# CH32V307V-R1-1v0.net
KiCad netlist of a schematic drawn in Altium Designer
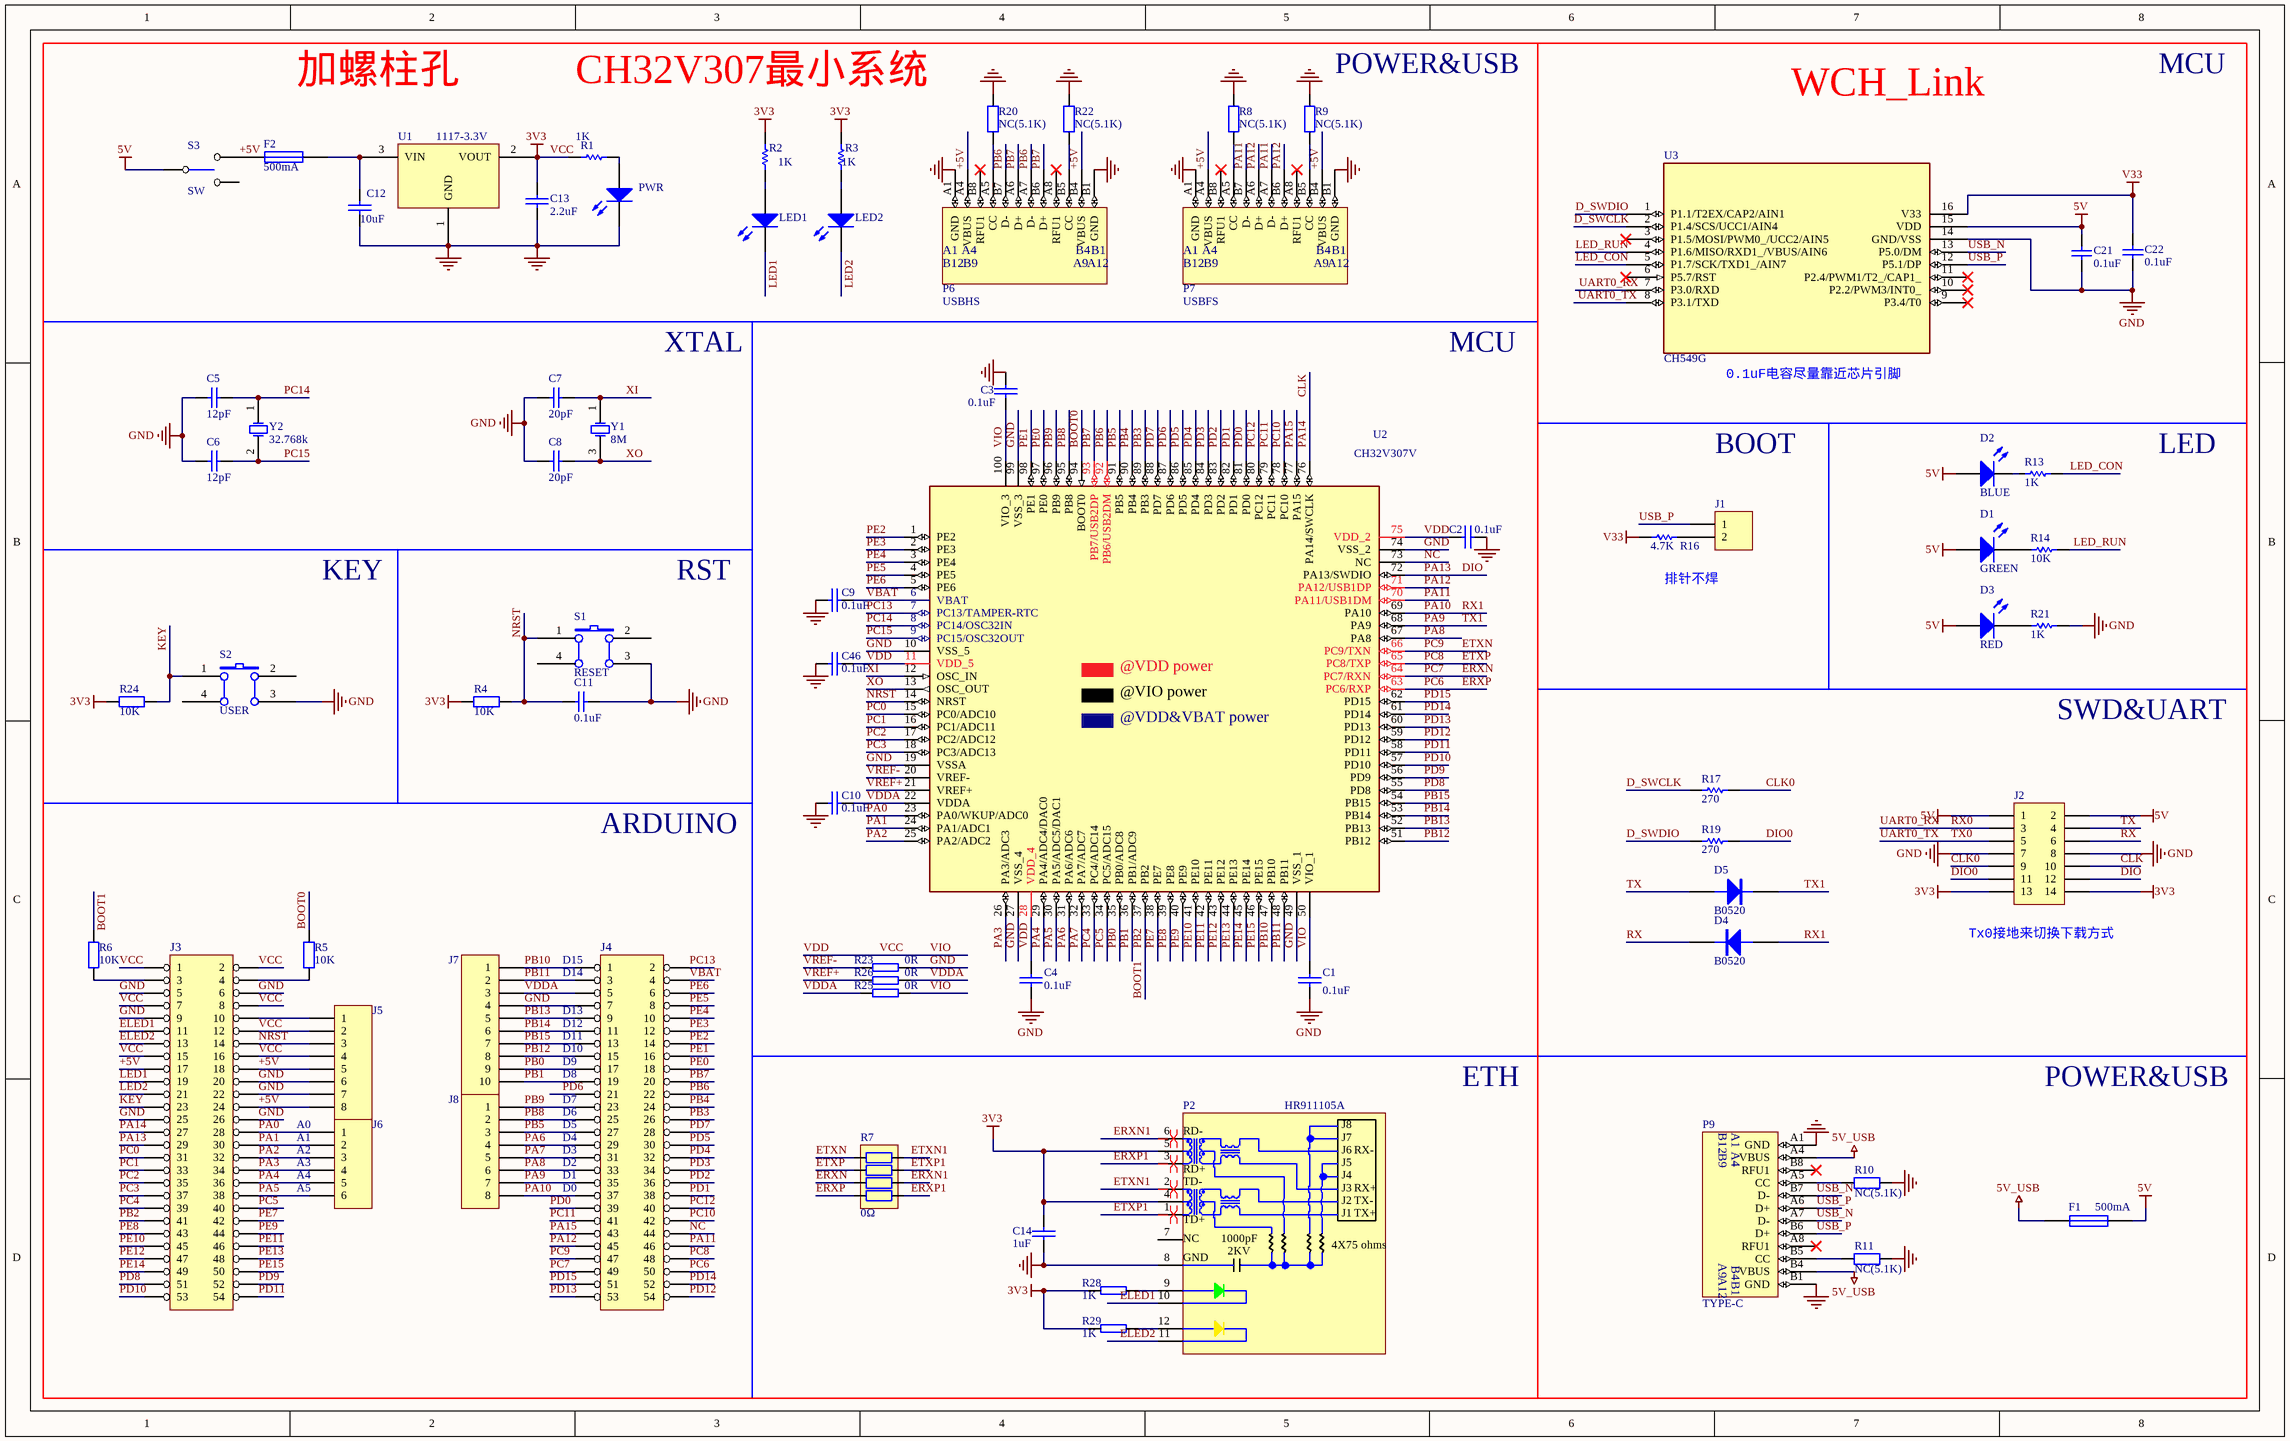
[diagram p0: CH32V307V-R1-1v0.SchDoc]

(export (version "E")
  (design (tool "Eeschema 10.0.6"))
  (components
    (comp (ref "C1")
      (value "0.1uF")
      (footprint "0603_C")
      (description "Capacitor")
      (libsource (lib "*") (part "CAP"))
    )
    (comp (ref "C2")
      (value "0.1uF")
      (footprint "0603_C")
      (description "Capacitor")
      (libsource (lib "*") (part "CAP"))
    )
    (comp (ref "C3")
      (value "0.1uF")
      (footprint "0603_C")
      (description "Capacitor")
      (libsource (lib "*") (part "CAP"))
    )
    (comp (ref "C4")
      (value "0.1uF")
      (footprint "0603_C")
      (description "Capacitor")
      (libsource (lib "*") (part "CAP"))
    )
    (comp (ref "C5")
      (value "12pF")
      (footprint "0603_C")
      (description "Capacitor")
      (libsource (lib "Miscellaneous Devices") (part "Cap"))
    )
    (comp (ref "C6")
      (value "12pF")
      (footprint "0603_C")
      (description "Capacitor")
      (libsource (lib "Miscellaneous Devices") (part "Cap"))
    )
    (comp (ref "C7")
      (value "20pF")
      (footprint "0603_C")
      (description "Capacitor")
      (libsource (lib "Miscellaneous Devices") (part "Cap"))
    )
    (comp (ref "C8")
      (value "20pF")
      (footprint "0603_C")
      (description "Capacitor")
      (libsource (lib "Miscellaneous Devices") (part "Cap"))
    )
    (comp (ref "C9")
      (value "0.1uF")
      (footprint "0603_C")
      (description "Capacitor")
      (libsource (lib "*") (part "CAP"))
    )
    (comp (ref "C10")
      (value "0.1uF")
      (footprint "0603_C")
      (description "Capacitor")
      (libsource (lib "*") (part "CAP"))
    )
    (comp (ref "C11")
      (value "0.1uF")
      (footprint "0603_C")
      (description "Capacitor")
      (libsource (lib "Miscellaneous Devices") (part "Cap"))
    )
    (comp (ref "C12")
      (value "10uF")
      (footprint "3216_C")
      (description "Capacitor")
      (libsource (lib "*") (part "CAP"))
    )
    (comp (ref "C13")
      (value "2.2uF")
      (footprint "0603_C")
      (description "Capacitor")
      (libsource (lib "*") (part "CAP"))
    )
    (comp (ref "C14")
      (value "1uF")
      (footprint "0603_C")
      (description "Capacitor")
      (libsource (lib "*") (part "CAP"))
    )
    (comp (ref "C21")
      (value "0.1uF")
      (footprint "0603_C")
      (description "Capacitor")
      (fields (field (name "PUBLISHER") "Altium Limited"))
      (libsource (lib "MYLIB") (part "C-RAD-0603"))
    )
    (comp (ref "C22")
      (value "0.1uF")
      (footprint "0603_C")
      (description "Capacitor")
      (fields (field (name "PUBLISHER") "Altium Limited"))
      (libsource (lib "MYLIB") (part "C-RAD-0603"))
    )
    (comp (ref "C46")
      (value "0.1uF")
      (footprint "0603_C")
      (description "Capacitor")
      (libsource (lib "*") (part "CAP"))
    )
    (comp (ref "D1")
      (value "GREEN")
      (footprint "0603+")
      (description "Typical RED, GREEN, YELLOW, AMBER GaAs LED")
      (fields (field (name "PUBLISHER") "Altium Limited"))
      (libsource (lib "MYLIB") (part "D0603"))
    )
    (comp (ref "D2")
      (value "BLUE")
      (footprint "0603+")
      (description "Typical RED, GREEN, YELLOW, AMBER GaAs LED")
      (fields (field (name "PUBLISHER") "Altium Limited"))
      (libsource (lib "MYLIB") (part "D0603"))
    )
    (comp (ref "D3")
      (value "RED")
      (footprint "0603+")
      (description "Typical RED, GREEN, YELLOW, AMBER GaAs LED")
      (fields (field (name "PUBLISHER") "Altium Limited"))
      (libsource (lib "MYLIB") (part "D0603"))
    )
    (comp (ref "D4")
      (value "B0520")
      (footprint "SOD-323")
      (description "Diode")
      (libsource (lib "*") (part "DIODE"))
    )
    (comp (ref "D5")
      (value "B0520")
      (footprint "SOD-323")
      (description "Diode")
      (libsource (lib "*") (part "DIODE"))
    )
    (comp (ref "F1")
      (value "500mA")
      (footprint "0805")
      (description "Fuse")
      (libsource (lib "*") (part "FUSE1"))
    )
    (comp (ref "F2")
      (value "500mA")
      (footprint "0805")
      (description "Fuse")
      (libsource (lib "*") (part "FUSE1"))
    )
    (comp (ref "J1")
      (value "Header 2")
      (footprint "SIP2-2.54MM")
      (description "Header, 2-Pin")
      (fields (field (name "PUBLISHER") "Altium Limited"))
      (libsource (lib "Miscellaneous Connectors") (part "Header 2"))
    )
    (comp (ref "J2")
      (value "Header 7X2")
      (footprint "IDC14-2.54mm")
      (description "Header, 7-Pin, Dual row")
      (fields (field (name "PUBLISHER") "Altium Limited"))
      (libsource (lib "Miscellaneous Connectors") (part "Header 7X2"))
    )
    (comp (ref "J3")
      (value "HEADER 27x2")
      (footprint "MYPCB:IDC54-2.54MM")
      (description "Header, 27-Pin, Dual row")
      (libsource (lib "wch_sch_others") (part "HEADER 27x2"))
    )
    (comp (ref "J4")
      (value "HEADER 27x2")
      (footprint "MYPCB:IDC54-2.54MM")
      (description "Header, 27-Pin, Dual row")
      (libsource (lib "wch_sch_others") (part "HEADER 27x2"))
    )
    (comp (ref "J5")
      (value "Header 8")
      (footprint "SIP8-2.54mm")
      (description "Header, 8-Pin")
      (fields (field (name "PUBLISHER") "Altium Limited"))
      (libsource (lib "") (part "Header 8_1"))
    )
    (comp (ref "J6")
      (value "Header 6")
      (footprint "SIP6-2.54MM")
      (description "Header, 6-Pin")
      (fields (field (name "PUBLISHER") "Altium Limited"))
      (libsource (lib "Miscellaneous Connectors") (part "Header 6"))
    )
    (comp (ref "J7")
      (value "Header 10")
      (footprint "SIP10-2.54mm")
      (description "Header, 10-Pin")
      (fields (field (name "PUBLISHER") "Altium Limited"))
      (libsource (lib "Miscellaneous Connectors") (part "Header 10"))
    )
    (comp (ref "J8")
      (value "Header 8")
      (footprint "SIP8-2.54mm")
      (description "Header, 8-Pin")
      (fields (field (name "PUBLISHER") "Altium Limited"))
      (libsource (lib "Miscellaneous Connectors") (part "Header 8"))
    )
    (comp (ref "LED1")
      (value "LED1   blue")
      (footprint "0603+")
      (description "Typical INFRARED GaAs LED")
      (fields (field (name "PUBLISHER") "Altium Limited"))
      (libsource (lib "Miscellaneous Devices") (part "LED0"))
    )
    (comp (ref "LED2")
      (value "LED2  blue")
      (footprint "0603+")
      (description "Typical INFRARED GaAs LED")
      (fields (field (name "PUBLISHER") "Altium Limited"))
      (libsource (lib "Miscellaneous Devices") (part "LED0"))
    )
    (comp (ref "P2") (value "HR911105A") (footprint "HR911105A") (libsource (lib "*") (part "HR911105A")))
    (comp (ref "P6")
      (value "USBHS")
      (footprint "TYPE-C-Receptacle-2.0")
      (libsource (lib "") (part "TYPE-C1_1"))
    )
    (comp (ref "P7")
      (value "USBFS")
      (footprint "TYPE-C-Receptacle-2.0")
      (libsource (lib "") (part "TYPE-C1_1"))
    )
    (comp (ref "P9")
      (value "TYPE-C")
      (footprint "TYPE-C-Receptacle-2.0")
      (libsource (lib "*") (part "TYPE-C1"))
    )
    (comp (ref "PWR")
      (value "POWER  red")
      (footprint "0603+")
      (description "Typical INFRARED GaAs LED")
      (fields (field (name "PUBLISHER") "Altium Limited"))
      (libsource (lib "Miscellaneous Devices") (part "LED0"))
    )
    (comp (ref "R1")
      (value "1K")
      (footprint "0603")
      (description "Semiconductor Resistor")
      (libsource (lib "Miscellaneous Devices") (part "Res Semi"))
    )
    (comp (ref "R2")
      (value "1K")
      (footprint "0603")
      (description "Semiconductor Resistor")
      (libsource (lib "Miscellaneous Devices") (part "Res Semi"))
    )
    (comp (ref "R3")
      (value "1K")
      (footprint "0603")
      (description "Semiconductor Resistor")
      (libsource (lib "Miscellaneous Devices") (part "Res Semi"))
    )
    (comp (ref "R4")
      (value "10K")
      (footprint "0603")
      (description "Resistor")
      (libsource (lib "") (part "Res2_2"))
    )
    (comp (ref "R5")
      (value "10K")
      (footprint "0603")
      (description "Resistor")
      (libsource (lib "") (part "Res2_1"))
    )
    (comp (ref "R6")
      (value "10K")
      (footprint "0603")
      (description "Resistor")
      (libsource (lib "Miscellaneous Devices") (part "Res2"))
    )
    (comp (ref "R7")
      (value "0Ω")
      (footprint "RCA-8P4R-0603")
      (description "贴片网络排阻")
      (fields (field (name "版权归属") "源创客"))
      (libsource (lib "wch_sch_others") (part "R-8P4R"))
    )
    (comp (ref "R8")
      (value "NC(5.1K)")
      (footprint "0603")
      (description "Resistor")
      (libsource (lib "Miscellaneous Devices") (part "Res2"))
    )
    (comp (ref "R9")
      (value "NC(5.1K)")
      (footprint "0603")
      (description "Resistor")
      (libsource (lib "Miscellaneous Devices") (part "Res2"))
    )
    (comp (ref "R10")
      (value "NC(5.1K)")
      (footprint "0603")
      (description "Resistor")
      (libsource (lib "") (part "Res2_3"))
    )
    (comp (ref "R11")
      (value "NC(5.1K)")
      (footprint "0603")
      (description "Resistor")
      (libsource (lib "") (part "Res2_3"))
    )
    (comp (ref "R13")
      (value "1K")
      (footprint "0603")
      (description "Resistor")
      (fields (field (name "PUBLISHER") "Altium Limited"))
      (libsource (lib "MYLIB") (part "0603-1"))
    )
    (comp (ref "R14")
      (value "10K")
      (footprint "0603")
      (description "Resistor")
      (fields (field (name "PUBLISHER") "Altium Limited"))
      (libsource (lib "MYLIB") (part "0603-1"))
    )
    (comp (ref "R16")
      (value "4.7K")
      (footprint "0603")
      (description "Resistor")
      (fields (field (name "PUBLISHER") "Altium Limited"))
      (libsource (lib "MYLIB") (part "0603-1"))
    )
    (comp (ref "R17")
      (value "270")
      (footprint "0603")
      (description "Resistor")
      (fields (field (name "PUBLISHER") "Altium Limited"))
      (libsource (lib "MYLIB") (part "0603-1"))
    )
    (comp (ref "R19")
      (value "270")
      (footprint "0603")
      (description "Resistor")
      (fields (field (name "PUBLISHER") "Altium Limited"))
      (libsource (lib "MYLIB") (part "0603-1"))
    )
    (comp (ref "R20")
      (value "NC(5.1K)")
      (footprint "0603")
      (description "Resistor")
      (libsource (lib "Miscellaneous Devices") (part "Res2"))
    )
    (comp (ref "R21")
      (value "1K")
      (footprint "0603")
      (description "Resistor")
      (fields (field (name "PUBLISHER") "Altium Limited"))
      (libsource (lib "MYLIB") (part "0603-1"))
    )
    (comp (ref "R22")
      (value "NC(5.1K)")
      (footprint "0603")
      (description "Resistor")
      (libsource (lib "Miscellaneous Devices") (part "Res2"))
    )
    (comp (ref "R23") (value "0R") (footprint "0603") (libsource (lib "*") (part "R")))
    (comp (ref "R24")
      (value "10K")
      (footprint "0603")
      (description "Resistor")
      (libsource (lib "") (part "Res2_2"))
    )
    (comp (ref "R25") (value "0R") (footprint "0603") (libsource (lib "*") (part "R")))
    (comp (ref "R26") (value "0R") (footprint "0603") (libsource (lib "*") (part "R")))
    (comp (ref "R28") (value "1K") (footprint "0603") (libsource (lib "wch_sch_others") (part "RES")))
    (comp (ref "R29") (value "1K") (footprint "0603") (libsource (lib "wch_sch_others") (part "RES")))
    (comp (ref "S1")
      (value "RESET")
      (footprint "KEYX")
      (description "SE PUSHBUTTON")
      (libsource (lib "Documents") (part "SW PUSHBUTTON"))
    )
    (comp (ref "S2")
      (value "USER")
      (footprint "KEYX")
      (description "SE PUSHBUTTON")
      (libsource (lib "Documents") (part "SW PUSHBUTTON"))
    )
    (comp (ref "S3") (value "SW") (footprint "KEY2") (libsource (lib "MYSCH") (part "SW")))
    (comp (ref "U1")
      (value "1117-3.3V")
      (footprint "SOT-223")
      (libsource (lib "wch_sch_others") (part "1117-3.3V"))
    )
    (comp (ref "U2")
      (value "CH32V307V")
      (footprint "LQFP100")
      (description "RISC-V FPU MCU, 144MHz, USB_480M，USB OTG,1000M Ethernet MAC, 2*CAN")
      (libsource (lib "CHXXX") (part "CH32V307V"))
    )
    (comp (ref "U3")
      (value "CH549G")
      (footprint "SOP16")
      (description "8bit MCS51 MCU with ADC & USB type-C host & device & dual UART & SPI")
      (libsource (lib "CHXXXSCH(1)") (part "CH549G"))
    )
    (comp (ref "Y1")
      (value "8M")
      (footprint "XT3225")
      (description "Crystal Oscillator")
      (fields (field (name "PUBLISHER") "Altium Limited"))
      (libsource (lib "") (part "XTAL_1"))
    )
    (comp (ref "Y2")
      (value "32.768k")
      (footprint "FC-135")
      (description "Crystal Oscillator")
      (fields (field (name "PUBLISHER") "Altium Limited"))
      (libsource (lib "Miscellaneous Devices") (part "XTAL"))
    )
  )
  (nets
    (net (code "1") (name "/+5V") (class "Default")
      (node (ref "F2") (pin "1") (pinfunction "1_1") (pintype "passive"))
      (node (ref "J3") (pin "17") (pinfunction "17_17") (pintype "passive"))
      (node (ref "J3") (pin "18") (pinfunction "18_18") (pintype "passive"))
      (node (ref "J3") (pin "24") (pinfunction "24_24") (pintype "passive"))
      (node (ref "J5") (pin "5") (pinfunction "5_5") (pintype "passive"))
      (node (ref "J5") (pin "8") (pinfunction "8_8") (pintype "passive"))
      (node (ref "P6") (pin "A4") (pinfunction "VBUS_A4") (pintype "bidirectional"))
      (node (ref "P6") (pin "B4") (pinfunction "VBUS_B4") (pintype "bidirectional"))
      (node (ref "P7") (pin "A4") (pinfunction "VBUS_A4") (pintype "bidirectional"))
      (node (ref "P7") (pin "B4") (pinfunction "VBUS_B4") (pintype "bidirectional"))
      (node (ref "S3") (pin "3") (pinfunction "3_3") (pintype "passive"))
    )
    (net (code "2") (name "/BOOT0") (class "Default")
      (node (ref "R5") (pin "2") (pinfunction "2_2") (pintype "passive"))
      (node (ref "U2") (pin "94") (pinfunction "BOOT0_94") (pintype "input"))
    )
    (net (code "3") (name "/BOOT1") (class "Default")
      (node (ref "J3") (pin "41") (pinfunction "41_41") (pintype "passive"))
      (node (ref "R6") (pin "1") (pinfunction "1_1") (pintype "passive"))
      (node (ref "U2") (pin "37") (pinfunction "PB2_37") (pintype "bidirectional"))
    )
    (net (code "4") (name "/CLK") (class "Default")
      (node (ref "J2") (pin "10") (pinfunction "10_10") (pintype "passive"))
      (node (ref "J3") (pin "27") (pinfunction "27_27") (pintype "passive"))
      (node (ref "U2") (pin "76") (pinfunction "PA14/SWCLK_76") (pintype "bidirectional"))
    )
    (net (code "5") (name "/CLK0") (class "Default")
      (node (ref "J2") (pin "9") (pinfunction "9_9") (pintype "passive"))
      (node (ref "R17") (pin "1") (pinfunction "1_1") (pintype "passive"))
    )
    (net (code "6") (name "/DIO") (class "Default")
      (node (ref "J2") (pin "12") (pinfunction "12_12") (pintype "passive"))
      (node (ref "J3") (pin "29") (pinfunction "29_29") (pintype "passive"))
      (node (ref "U2") (pin "72") (pinfunction "PA13/SWDIO_72") (pintype "bidirectional"))
    )
    (net (code "7") (name "/DIO0") (class "Default")
      (node (ref "J2") (pin "11") (pinfunction "11_11") (pintype "passive"))
      (node (ref "R19") (pin "1") (pinfunction "1_1") (pintype "passive"))
    )
    (net (code "8") (name "/D_SWCLK") (class "Default")
      (node (ref "R17") (pin "2") (pinfunction "2_2") (pintype "passive"))
      (node (ref "U3") (pin "2") (pinfunction "P1.4/SCS/UCC1/AIN4_2") (pintype "bidirectional"))
    )
    (net (code "9") (name "/D_SWDIO") (class "Default")
      (node (ref "R19") (pin "2") (pinfunction "2_2") (pintype "passive"))
      (node (ref "U3") (pin "1") (pinfunction "P1.1/T2EX/CAP2/AIN1_1") (pintype "bidirectional"))
    )
    (net (code "10") (name "/ELED1") (class "Default")
      (node (ref "J3") (pin "11") (pinfunction "11_11") (pintype "passive"))
      (node (ref "P2") (pin "10") (pintype "passive"))
    )
    (net (code "11") (name "/ELED2") (class "Default")
      (node (ref "J3") (pin "13") (pinfunction "13_13") (pintype "passive"))
      (node (ref "P2") (pin "11") (pintype "passive"))
    )
    (net (code "12") (name "/ERXN") (class "Default")
      (node (ref "J4") (pin "49") (pinfunction "49_49") (pintype "passive"))
      (node (ref "R7") (pin "3") (pinfunction "3_3") (pintype "passive"))
      (node (ref "U2") (pin "64") (pinfunction "PC7/RXN_64") (pintype "bidirectional"))
    )
    (net (code "13") (name "/ERXN1") (class "Default")
      (node (ref "P2") (pin "6") (pintype "passive"))
      (node (ref "R7") (pin "6") (pinfunction "6_6") (pintype "passive"))
    )
    (net (code "14") (name "/ERXP") (class "Default")
      (node (ref "J4") (pin "50") (pinfunction "50_50") (pintype "passive"))
      (node (ref "R7") (pin "4") (pinfunction "4_4") (pintype "passive"))
      (node (ref "U2") (pin "63") (pinfunction "PC6/RXP_63") (pintype "bidirectional"))
    )
    (net (code "15") (name "/ERXP1") (class "Default")
      (node (ref "P2") (pin "3") (pintype "passive"))
      (node (ref "R7") (pin "5") (pinfunction "5_5") (pintype "passive"))
    )
    (net (code "16") (name "/ETXN") (class "Default")
      (node (ref "J4") (pin "47") (pinfunction "47_47") (pintype "passive"))
      (node (ref "R7") (pin "1") (pinfunction "1_1") (pintype "passive"))
      (node (ref "U2") (pin "66") (pinfunction "PC9/TXN_66") (pintype "bidirectional"))
    )
    (net (code "17") (name "/ETXN1") (class "Default")
      (node (ref "P2") (pin "2") (pintype "passive"))
      (node (ref "R7") (pin "8") (pinfunction "8_8") (pintype "passive"))
    )
    (net (code "18") (name "/ETXP") (class "Default")
      (node (ref "J4") (pin "48") (pinfunction "48_48") (pintype "passive"))
      (node (ref "R7") (pin "2") (pinfunction "2_2") (pintype "passive"))
      (node (ref "U2") (pin "65") (pinfunction "PC8/TXP_65") (pintype "bidirectional"))
    )
    (net (code "19") (name "/ETXP1") (class "Default")
      (node (ref "P2") (pin "1") (pintype "passive"))
      (node (ref "R7") (pin "7") (pinfunction "7_7") (pintype "passive"))
    )
    (net (code "20") (name "/KEY") (class "Default")
      (node (ref "J3") (pin "23") (pinfunction "23_23") (pintype "passive"))
      (node (ref "R24") (pin "1") (pinfunction "1_1") (pintype "passive"))
      (node (ref "S2") (pin "1") (pinfunction "A0_1") (pintype "passive"))
    )
    (net (code "21") (name "/LED1") (class "Default")
      (node (ref "J3") (pin "19") (pinfunction "19_19") (pintype "passive"))
      (node (ref "LED1") (pin "2") (pinfunction "K_2") (pintype "passive"))
    )
    (net (code "22") (name "/LED2") (class "Default")
      (node (ref "J3") (pin "21") (pinfunction "21_21") (pintype "passive"))
      (node (ref "LED2") (pin "2") (pinfunction "K_2") (pintype "passive"))
    )
    (net (code "23") (name "/LED_CON") (class "Default")
      (node (ref "R13") (pin "1") (pinfunction "1_1") (pintype "passive"))
      (node (ref "U3") (pin "5") (pinfunction "P1.7/SCK/TXD1_/AIN7_5") (pintype "bidirectional"))
    )
    (net (code "24") (name "/LED_RUN") (class "Default")
      (node (ref "R14") (pin "1") (pinfunction "1_1") (pintype "passive"))
      (node (ref "U3") (pin "4") (pinfunction "P1.6/MISO/RXD1_/VBUS/AIN6_4") (pintype "bidirectional"))
    )
    (net (code "25") (name "/NC") (class "Default")
      (node (ref "J4") (pin "44") (pinfunction "44_44") (pintype "passive"))
      (node (ref "U2") (pin "73") (pinfunction "NC_73") (pintype "tri_state"))
    )
    (net (code "26") (name "/NRST") (class "Default")
      (node (ref "C11") (pin "2") (pinfunction "2_2") (pintype "passive"))
      (node (ref "J3") (pin "14") (pinfunction "14_14") (pintype "passive"))
      (node (ref "J5") (pin "3") (pinfunction "3_3") (pintype "passive"))
      (node (ref "R4") (pin "1") (pinfunction "1_1") (pintype "passive"))
      (node (ref "S1") (pin "1") (pinfunction "A0_1") (pintype "passive"))
      (node (ref "U2") (pin "14") (pinfunction "NRST_14") (pintype "bidirectional"))
    )
    (net (code "27") (name "/PA0") (class "Default")
      (node (ref "J3") (pin "28") (pinfunction "28_28") (pintype "passive"))
      (node (ref "J6") (pin "1") (pinfunction "1_1") (pintype "passive"))
      (node (ref "U2") (pin "23") (pinfunction "PA0/WKUP/ADC0_23") (pintype "bidirectional"))
    )
    (net (code "28") (name "/PA1") (class "Default")
      (node (ref "J3") (pin "30") (pinfunction "30_30") (pintype "passive"))
      (node (ref "J6") (pin "2") (pinfunction "2_2") (pintype "passive"))
      (node (ref "U2") (pin "24") (pinfunction "PA1/ADC1_24") (pintype "bidirectional"))
    )
    (net (code "29") (name "/PA2") (class "Default")
      (node (ref "J3") (pin "32") (pinfunction "32_32") (pintype "passive"))
      (node (ref "J6") (pin "3") (pinfunction "3_3") (pintype "passive"))
      (node (ref "U2") (pin "25") (pinfunction "PA2/ADC2_25") (pintype "bidirectional"))
    )
    (net (code "30") (name "/PA3") (class "Default")
      (node (ref "J3") (pin "34") (pinfunction "34_34") (pintype "passive"))
      (node (ref "J6") (pin "4") (pinfunction "4_4") (pintype "passive"))
      (node (ref "U2") (pin "26") (pinfunction "PA3/ADC3_26") (pintype "bidirectional"))
    )
    (net (code "31") (name "/PA4") (class "Default")
      (node (ref "J3") (pin "36") (pinfunction "36_36") (pintype "passive"))
      (node (ref "J6") (pin "5") (pinfunction "5_5") (pintype "passive"))
      (node (ref "U2") (pin "29") (pinfunction "PA4/ADC4/DAC0_29") (pintype "bidirectional"))
    )
    (net (code "32") (name "/PA5") (class "Default")
      (node (ref "J3") (pin "38") (pinfunction "38_38") (pintype "passive"))
      (node (ref "J6") (pin "6") (pinfunction "6_6") (pintype "passive"))
      (node (ref "U2") (pin "30") (pinfunction "PA5/ADC5/DAC1_30") (pintype "bidirectional"))
    )
    (net (code "33") (name "/PA6") (class "Default")
      (node (ref "J4") (pin "29") (pinfunction "29_29") (pintype "passive"))
      (node (ref "J8") (pin "4") (pinfunction "4_4") (pintype "passive"))
      (node (ref "U2") (pin "31") (pinfunction "PA6/ADC6_31") (pintype "bidirectional"))
    )
    (net (code "34") (name "/PA7") (class "Default")
      (node (ref "J4") (pin "31") (pinfunction "31_31") (pintype "passive"))
      (node (ref "J8") (pin "5") (pinfunction "5_5") (pintype "passive"))
      (node (ref "U2") (pin "32") (pinfunction "PA7/ADC7_32") (pintype "bidirectional"))
    )
    (net (code "35") (name "/PA8") (class "Default")
      (node (ref "J4") (pin "33") (pinfunction "33_33") (pintype "passive"))
      (node (ref "J8") (pin "6") (pinfunction "6_6") (pintype "passive"))
      (node (ref "U2") (pin "67") (pinfunction "PA8_67") (pintype "bidirectional"))
    )
    (net (code "36") (name "/PA9") (class "Default")
      (node (ref "D5") (pin "2") (pinfunction "K_2") (pintype "passive"))
      (node (ref "J4") (pin "35") (pinfunction "35_35") (pintype "passive"))
      (node (ref "J8") (pin "7") (pinfunction "7_7") (pintype "passive"))
      (node (ref "U2") (pin "68") (pinfunction "PA9_68") (pintype "bidirectional"))
    )
    (net (code "37") (name "/PA10") (class "Default")
      (node (ref "D4") (pin "1") (pinfunction "A_1") (pintype "passive"))
      (node (ref "J4") (pin "37") (pinfunction "37_37") (pintype "passive"))
      (node (ref "J8") (pin "8") (pinfunction "8_8") (pintype "passive"))
      (node (ref "U2") (pin "69") (pinfunction "PA10_69") (pintype "bidirectional"))
    )
    (net (code "38") (name "/PA11") (class "Default")
      (node (ref "J4") (pin "46") (pinfunction "46_46") (pintype "passive"))
      (node (ref "P7") (pin "A7") (pinfunction "D-_A7") (pintype "bidirectional"))
      (node (ref "P7") (pin "B7") (pinfunction "D-_B7") (pintype "bidirectional"))
      (node (ref "U2") (pin "70") (pinfunction "PA11/USB1DM_70") (pintype "bidirectional"))
    )
    (net (code "39") (name "/PA12") (class "Default")
      (node (ref "J4") (pin "45") (pinfunction "45_45") (pintype "passive"))
      (node (ref "P7") (pin "A6") (pinfunction "D+_A6") (pintype "bidirectional"))
      (node (ref "P7") (pin "B6") (pinfunction "D+_B6") (pintype "bidirectional"))
      (node (ref "U2") (pin "71") (pinfunction "PA12/USB1DP_71") (pintype "bidirectional"))
    )
    (net (code "40") (name "/PA15") (class "Default")
      (node (ref "J4") (pin "43") (pinfunction "43_43") (pintype "passive"))
      (node (ref "U2") (pin "77") (pinfunction "PA15_77") (pintype "bidirectional"))
    )
    (net (code "41") (name "/PB0") (class "Default")
      (node (ref "J4") (pin "17") (pinfunction "17_17") (pintype "passive"))
      (node (ref "J7") (pin "9") (pinfunction "9_9") (pintype "passive"))
      (node (ref "U2") (pin "35") (pinfunction "PB0/ADC8_35") (pintype "bidirectional"))
    )
    (net (code "42") (name "/PB1") (class "Default")
      (node (ref "J4") (pin "19") (pinfunction "19_19") (pintype "passive"))
      (node (ref "J7") (pin "10") (pinfunction "10_10") (pintype "passive"))
      (node (ref "U2") (pin "36") (pinfunction "PB1/ADC9_36") (pintype "bidirectional"))
    )
    (net (code "43") (name "/PB3") (class "Default")
      (node (ref "J4") (pin "26") (pinfunction "26_26") (pintype "passive"))
      (node (ref "U2") (pin "89") (pinfunction "PB3_89") (pintype "bidirectional"))
    )
    (net (code "44") (name "/PB4") (class "Default")
      (node (ref "J4") (pin "24") (pinfunction "24_24") (pintype "passive"))
      (node (ref "U2") (pin "90") (pinfunction "PB4_90") (pintype "bidirectional"))
    )
    (net (code "45") (name "/PB5") (class "Default")
      (node (ref "J4") (pin "27") (pinfunction "27_27") (pintype "passive"))
      (node (ref "J8") (pin "3") (pinfunction "3_3") (pintype "passive"))
      (node (ref "U2") (pin "91") (pinfunction "PB5_91") (pintype "bidirectional"))
    )
    (net (code "46") (name "/PB6") (class "Default")
      (node (ref "J4") (pin "22") (pinfunction "22_22") (pintype "passive"))
      (node (ref "P6") (pin "A7") (pinfunction "D-_A7") (pintype "bidirectional"))
      (node (ref "P6") (pin "B7") (pinfunction "D-_B7") (pintype "bidirectional"))
      (node (ref "U2") (pin "92") (pinfunction "PB6/USB2DM_92") (pintype "bidirectional"))
    )
    (net (code "47") (name "/PB7") (class "Default")
      (node (ref "J4") (pin "20") (pinfunction "20_20") (pintype "passive"))
      (node (ref "P6") (pin "A6") (pinfunction "D+_A6") (pintype "bidirectional"))
      (node (ref "P6") (pin "B6") (pinfunction "D+_B6") (pintype "bidirectional"))
      (node (ref "U2") (pin "93") (pinfunction "PB7/USB2DP_93") (pintype "bidirectional"))
    )
    (net (code "48") (name "/PB8") (class "Default")
      (node (ref "J4") (pin "25") (pinfunction "25_25") (pintype "passive"))
      (node (ref "J8") (pin "2") (pinfunction "2_2") (pintype "passive"))
      (node (ref "U2") (pin "95") (pinfunction "PB8_95") (pintype "bidirectional"))
    )
    (net (code "49") (name "/PB9") (class "Default")
      (node (ref "J4") (pin "23") (pinfunction "23_23") (pintype "passive"))
      (node (ref "J8") (pin "1") (pinfunction "1_1") (pintype "passive"))
      (node (ref "U2") (pin "96") (pinfunction "PB9_96") (pintype "bidirectional"))
    )
    (net (code "50") (name "/PB10") (class "Default")
      (node (ref "J4") (pin "1") (pinfunction "1_1") (pintype "passive"))
      (node (ref "J7") (pin "1") (pinfunction "1_1") (pintype "passive"))
      (node (ref "U2") (pin "47") (pinfunction "PB10_47") (pintype "bidirectional"))
    )
    (net (code "51") (name "/PB11") (class "Default")
      (node (ref "J4") (pin "3") (pinfunction "3_3") (pintype "passive"))
      (node (ref "J7") (pin "2") (pinfunction "2_2") (pintype "passive"))
      (node (ref "U2") (pin "48") (pinfunction "PB11_48") (pintype "bidirectional"))
    )
    (net (code "52") (name "/PB12") (class "Default")
      (node (ref "J4") (pin "15") (pinfunction "15_15") (pintype "passive"))
      (node (ref "J7") (pin "8") (pinfunction "8_8") (pintype "passive"))
      (node (ref "U2") (pin "51") (pinfunction "PB12_51") (pintype "bidirectional"))
    )
    (net (code "53") (name "/PB13") (class "Default")
      (node (ref "J4") (pin "9") (pinfunction "9_9") (pintype "passive"))
      (node (ref "J7") (pin "5") (pinfunction "5_5") (pintype "passive"))
      (node (ref "U2") (pin "52") (pinfunction "PB13_52") (pintype "bidirectional"))
    )
    (net (code "54") (name "/PB14") (class "Default")
      (node (ref "J4") (pin "11") (pinfunction "11_11") (pintype "passive"))
      (node (ref "J7") (pin "6") (pinfunction "6_6") (pintype "passive"))
      (node (ref "U2") (pin "53") (pinfunction "PB14_53") (pintype "bidirectional"))
    )
    (net (code "55") (name "/PB15") (class "Default")
      (node (ref "J4") (pin "13") (pinfunction "13_13") (pintype "passive"))
      (node (ref "J7") (pin "7") (pinfunction "7_7") (pintype "passive"))
      (node (ref "U2") (pin "54") (pinfunction "PB15_54") (pintype "bidirectional"))
    )
    (net (code "56") (name "/PC0") (class "Default")
      (node (ref "J3") (pin "31") (pinfunction "31_31") (pintype "passive"))
      (node (ref "U2") (pin "15") (pinfunction "PC0/ADC10_15") (pintype "bidirectional"))
    )
    (net (code "57") (name "/PC1") (class "Default")
      (node (ref "J3") (pin "33") (pinfunction "33_33") (pintype "passive"))
      (node (ref "U2") (pin "16") (pinfunction "PC1/ADC11_16") (pintype "bidirectional"))
    )
    (net (code "58") (name "/PC2") (class "Default")
      (node (ref "J3") (pin "35") (pinfunction "35_35") (pintype "passive"))
      (node (ref "U2") (pin "17") (pinfunction "PC2/ADC12_17") (pintype "bidirectional"))
    )
    (net (code "59") (name "/PC3") (class "Default")
      (node (ref "J3") (pin "37") (pinfunction "37_37") (pintype "passive"))
      (node (ref "U2") (pin "18") (pinfunction "PC3/ADC13_18") (pintype "bidirectional"))
    )
    (net (code "60") (name "/PC4") (class "Default")
      (node (ref "J3") (pin "39") (pinfunction "39_39") (pintype "passive"))
      (node (ref "U2") (pin "33") (pinfunction "PC4/ADC14_33") (pintype "bidirectional"))
    )
    (net (code "61") (name "/PC5") (class "Default")
      (node (ref "J3") (pin "40") (pinfunction "40_40") (pintype "passive"))
      (node (ref "U2") (pin "34") (pinfunction "PC5/ADC15_34") (pintype "bidirectional"))
    )
    (net (code "62") (name "/PC10") (class "Default")
      (node (ref "J4") (pin "42") (pinfunction "42_42") (pintype "passive"))
      (node (ref "U2") (pin "78") (pinfunction "PC10_78") (pintype "bidirectional"))
    )
    (net (code "63") (name "/PC11") (class "Default")
      (node (ref "J4") (pin "41") (pinfunction "41_41") (pintype "passive"))
      (node (ref "U2") (pin "79") (pinfunction "PC11_79") (pintype "bidirectional"))
    )
    (net (code "64") (name "/PC12") (class "Default")
      (node (ref "J4") (pin "40") (pinfunction "40_40") (pintype "passive"))
      (node (ref "U2") (pin "80") (pinfunction "PC12_80") (pintype "bidirectional"))
    )
    (net (code "65") (name "/PC13") (class "Default")
      (node (ref "J4") (pin "2") (pinfunction "2_2") (pintype "passive"))
      (node (ref "U2") (pin "7") (pinfunction "PC13/TAMPER-RTC_7") (pintype "bidirectional"))
    )
    (net (code "66") (name "/PC14") (class "Default")
      (node (ref "C5") (pin "1") (pinfunction "1_1") (pintype "passive"))
      (node (ref "U2") (pin "8") (pinfunction "PC14/OSC32IN_8") (pintype "bidirectional"))
      (node (ref "Y2") (pin "1") (pinfunction "OSC1_1") (pintype "passive"))
    )
    (net (code "67") (name "/PC15") (class "Default")
      (node (ref "C6") (pin "1") (pinfunction "1_1") (pintype "passive"))
      (node (ref "U2") (pin "9") (pinfunction "PC15/OSC32OUT_9") (pintype "bidirectional"))
      (node (ref "Y2") (pin "2") (pinfunction "OSC2_2") (pintype "passive"))
    )
    (net (code "68") (name "/PD0") (class "Default")
      (node (ref "J4") (pin "39") (pinfunction "39_39") (pintype "passive"))
      (node (ref "U2") (pin "81") (pinfunction "PD0_81") (pintype "bidirectional"))
    )
    (net (code "69") (name "/PD1") (class "Default")
      (node (ref "J4") (pin "38") (pinfunction "38_38") (pintype "passive"))
      (node (ref "U2") (pin "82") (pinfunction "PD1_82") (pintype "bidirectional"))
    )
    (net (code "70") (name "/PD2") (class "Default")
      (node (ref "J4") (pin "36") (pinfunction "36_36") (pintype "passive"))
      (node (ref "U2") (pin "83") (pinfunction "PD2_83") (pintype "bidirectional"))
    )
    (net (code "71") (name "/PD3") (class "Default")
      (node (ref "J4") (pin "34") (pinfunction "34_34") (pintype "passive"))
      (node (ref "U2") (pin "84") (pinfunction "PD3_84") (pintype "bidirectional"))
    )
    (net (code "72") (name "/PD4") (class "Default")
      (node (ref "J4") (pin "32") (pinfunction "32_32") (pintype "passive"))
      (node (ref "U2") (pin "85") (pinfunction "PD4_85") (pintype "bidirectional"))
    )
    (net (code "73") (name "/PD5") (class "Default")
      (node (ref "J4") (pin "30") (pinfunction "30_30") (pintype "passive"))
      (node (ref "U2") (pin "86") (pinfunction "PD5_86") (pintype "bidirectional"))
    )
    (net (code "74") (name "/PD6") (class "Default")
      (node (ref "J4") (pin "21") (pinfunction "21_21") (pintype "passive"))
      (node (ref "U2") (pin "87") (pinfunction "PD6_87") (pintype "bidirectional"))
    )
    (net (code "75") (name "/PD7") (class "Default")
      (node (ref "J4") (pin "28") (pinfunction "28_28") (pintype "passive"))
      (node (ref "U2") (pin "88") (pinfunction "PD7_88") (pintype "bidirectional"))
    )
    (net (code "76") (name "/PD8") (class "Default")
      (node (ref "J3") (pin "51") (pinfunction "51_51") (pintype "passive"))
      (node (ref "U2") (pin "55") (pinfunction "PD8_55") (pintype "bidirectional"))
    )
    (net (code "77") (name "/PD9") (class "Default")
      (node (ref "J3") (pin "52") (pinfunction "52_52") (pintype "passive"))
      (node (ref "U2") (pin "56") (pinfunction "PD9_56") (pintype "bidirectional"))
    )
    (net (code "78") (name "/PD10") (class "Default")
      (node (ref "J3") (pin "53") (pinfunction "53_53") (pintype "passive"))
      (node (ref "U2") (pin "57") (pinfunction "PD10_57") (pintype "bidirectional"))
    )
    (net (code "79") (name "/PD11") (class "Default")
      (node (ref "J3") (pin "54") (pinfunction "54_54") (pintype "passive"))
      (node (ref "U2") (pin "58") (pinfunction "PD11_58") (pintype "bidirectional"))
    )
    (net (code "80") (name "/PD12") (class "Default")
      (node (ref "J4") (pin "54") (pinfunction "54_54") (pintype "passive"))
      (node (ref "U2") (pin "59") (pinfunction "PD12_59") (pintype "bidirectional"))
    )
    (net (code "81") (name "/PD13") (class "Default")
      (node (ref "J4") (pin "53") (pinfunction "53_53") (pintype "passive"))
      (node (ref "U2") (pin "60") (pinfunction "PD13_60") (pintype "bidirectional"))
    )
    (net (code "82") (name "/PD14") (class "Default")
      (node (ref "J4") (pin "52") (pinfunction "52_52") (pintype "passive"))
      (node (ref "U2") (pin "61") (pinfunction "PD14_61") (pintype "bidirectional"))
    )
    (net (code "83") (name "/PD15") (class "Default")
      (node (ref "J4") (pin "51") (pinfunction "51_51") (pintype "passive"))
      (node (ref "U2") (pin "62") (pinfunction "PD15_62") (pintype "bidirectional"))
    )
    (net (code "84") (name "/PE0") (class "Default")
      (node (ref "J4") (pin "18") (pinfunction "18_18") (pintype "passive"))
      (node (ref "U2") (pin "97") (pinfunction "PE0_97") (pintype "bidirectional"))
    )
    (net (code "85") (name "/PE1") (class "Default")
      (node (ref "J4") (pin "16") (pinfunction "16_16") (pintype "passive"))
      (node (ref "U2") (pin "98") (pinfunction "PE1_98") (pintype "bidirectional"))
    )
    (net (code "86") (name "/PE2") (class "Default")
      (node (ref "J4") (pin "14") (pinfunction "14_14") (pintype "passive"))
      (node (ref "U2") (pin "1") (pinfunction "PE2_1") (pintype "bidirectional"))
    )
    (net (code "87") (name "/PE3") (class "Default")
      (node (ref "J4") (pin "12") (pinfunction "12_12") (pintype "passive"))
      (node (ref "U2") (pin "2") (pinfunction "PE3_2") (pintype "bidirectional"))
    )
    (net (code "88") (name "/PE4") (class "Default")
      (node (ref "J4") (pin "10") (pinfunction "10_10") (pintype "passive"))
      (node (ref "U2") (pin "3") (pinfunction "PE4_3") (pintype "bidirectional"))
    )
    (net (code "89") (name "/PE5") (class "Default")
      (node (ref "J4") (pin "8") (pinfunction "8_8") (pintype "passive"))
      (node (ref "U2") (pin "4") (pinfunction "PE5_4") (pintype "bidirectional"))
    )
    (net (code "90") (name "/PE6") (class "Default")
      (node (ref "J4") (pin "6") (pinfunction "6_6") (pintype "passive"))
      (node (ref "U2") (pin "5") (pinfunction "PE6_5") (pintype "bidirectional"))
    )
    (net (code "91") (name "/PE7") (class "Default")
      (node (ref "J3") (pin "42") (pinfunction "42_42") (pintype "passive"))
      (node (ref "U2") (pin "38") (pinfunction "PE7_38") (pintype "bidirectional"))
    )
    (net (code "92") (name "/PE8") (class "Default")
      (node (ref "J3") (pin "43") (pinfunction "43_43") (pintype "passive"))
      (node (ref "U2") (pin "39") (pinfunction "PE8_39") (pintype "bidirectional"))
    )
    (net (code "93") (name "/PE9") (class "Default")
      (node (ref "J3") (pin "44") (pinfunction "44_44") (pintype "passive"))
      (node (ref "U2") (pin "40") (pinfunction "PE9_40") (pintype "bidirectional"))
    )
    (net (code "94") (name "/PE10") (class "Default")
      (node (ref "J3") (pin "45") (pinfunction "45_45") (pintype "passive"))
      (node (ref "U2") (pin "41") (pinfunction "PE10_41") (pintype "bidirectional"))
    )
    (net (code "95") (name "/PE11") (class "Default")
      (node (ref "J3") (pin "46") (pinfunction "46_46") (pintype "passive"))
      (node (ref "U2") (pin "42") (pinfunction "PE11_42") (pintype "bidirectional"))
    )
    (net (code "96") (name "/PE12") (class "Default")
      (node (ref "J3") (pin "47") (pinfunction "47_47") (pintype "passive"))
      (node (ref "U2") (pin "43") (pinfunction "PE12_43") (pintype "bidirectional"))
    )
    (net (code "97") (name "/PE13") (class "Default")
      (node (ref "J3") (pin "48") (pinfunction "48_48") (pintype "passive"))
      (node (ref "U2") (pin "44") (pinfunction "PE13_44") (pintype "bidirectional"))
    )
    (net (code "98") (name "/PE14") (class "Default")
      (node (ref "J3") (pin "49") (pinfunction "49_49") (pintype "passive"))
      (node (ref "U2") (pin "45") (pinfunction "PE14_45") (pintype "bidirectional"))
    )
    (net (code "99") (name "/PE15") (class "Default")
      (node (ref "J3") (pin "50") (pinfunction "50_50") (pintype "passive"))
      (node (ref "U2") (pin "46") (pinfunction "PE15_46") (pintype "bidirectional"))
    )
    (net (code "100") (name "/RX") (class "Default")
      (node (ref "D4") (pin "2") (pinfunction "K_2") (pintype "passive"))
      (node (ref "J2") (pin "6") (pinfunction "6_6") (pintype "passive"))
    )
    (net (code "101") (name "/RX0") (class "Default")
      (node (ref "J2") (pin "3") (pinfunction "3_3") (pintype "passive"))
      (node (ref "U3") (pin "7") (pinfunction "P3.0/RXD_7") (pintype "bidirectional"))
    )
    (net (code "102") (name "/TX") (class "Default")
      (node (ref "D5") (pin "1") (pinfunction "A_1") (pintype "passive"))
      (node (ref "J2") (pin "4") (pinfunction "4_4") (pintype "passive"))
    )
    (net (code "103") (name "/TX0") (class "Default")
      (node (ref "J2") (pin "5") (pinfunction "5_5") (pintype "passive"))
      (node (ref "U3") (pin "8") (pinfunction "P3.1/TXD_8") (pintype "bidirectional"))
    )
    (net (code "104") (name "/USB_N") (class "Default")
      (node (ref "P9") (pin "A7") (pinfunction "D-_A7") (pintype "bidirectional"))
      (node (ref "P9") (pin "B7") (pinfunction "D-_B7") (pintype "bidirectional"))
      (node (ref "U3") (pin "13") (pinfunction "P5.0/DM_13") (pintype "bidirectional"))
    )
    (net (code "105") (name "/USB_P") (class "Default")
      (node (ref "J1") (pin "1") (pinfunction "1_1") (pintype "passive"))
      (node (ref "P9") (pin "A6") (pinfunction "D+_A6") (pintype "bidirectional"))
      (node (ref "P9") (pin "B6") (pinfunction "D+_B6") (pintype "bidirectional"))
      (node (ref "U3") (pin "12") (pinfunction "P5.1/DP_12") (pintype "bidirectional"))
    )
    (net (code "106") (name "/VBAT") (class "Default")
      (node (ref "C9") (pin "2") (pinfunction "2_2") (pintype "passive"))
      (node (ref "J4") (pin "4") (pinfunction "4_4") (pintype "passive"))
      (node (ref "U2") (pin "6") (pinfunction "VBAT_6") (pintype "power_in"))
    )
    (net (code "107") (name "/VDDA") (class "Default")
      (node (ref "C10") (pin "2") (pinfunction "2_2") (pintype "passive"))
      (node (ref "J4") (pin "5") (pinfunction "5_5") (pintype "passive"))
      (node (ref "J7") (pin "3") (pinfunction "3_3") (pintype "passive"))
      (node (ref "R25") (pin "2") (pinfunction "2_2") (pintype "passive"))
      (node (ref "R26") (pin "1") (pinfunction "1_1") (pintype "passive"))
      (node (ref "U2") (pin "22") (pinfunction "VDDA_22") (pintype "power_in"))
    )
    (net (code "108") (name "/VREF+") (class "Default")
      (node (ref "R26") (pin "2") (pinfunction "2_2") (pintype "passive"))
      (node (ref "U2") (pin "21") (pinfunction "VREF+_21") (pintype "power_in"))
    )
    (net (code "109") (name "/VREF-") (class "Default")
      (node (ref "R23") (pin "2") (pinfunction "2_2") (pintype "passive"))
      (node (ref "U2") (pin "20") (pinfunction "VREF-_20") (pintype "power_in"))
    )
    (net (code "110") (name "/XI") (class "Default")
      (node (ref "C7") (pin "2") (pinfunction "2_2") (pintype "passive"))
      (node (ref "U2") (pin "12") (pinfunction "OSC_IN_12") (pintype "input"))
      (node (ref "Y1") (pin "1") (pinfunction "OSC1_1") (pintype "passive"))
    )
    (net (code "111") (name "/XO") (class "Default")
      (node (ref "C8") (pin "2") (pinfunction "2_2") (pintype "passive"))
      (node (ref "U2") (pin "13") (pinfunction "OSC_OUT_13") (pintype "output"))
      (node (ref "Y1") (pin "3") (pinfunction "OSC2_3") (pintype "passive"))
    )
    (net (code "112") (name "3V3") (class "Default")
      (node (ref "C1") (pin "2") (pinfunction "2_2") (pintype "passive"))
      (node (ref "C13") (pin "1") (pinfunction "1_1") (pintype "passive"))
      (node (ref "C14") (pin "2") (pinfunction "2_2") (pintype "passive"))
      (node (ref "C2") (pin "2") (pinfunction "2_2") (pintype "passive"))
      (node (ref "C3") (pin "1") (pinfunction "1_1") (pintype "passive"))
      (node (ref "C4") (pin "2") (pinfunction "2_2") (pintype "passive"))
      (node (ref "C46") (pin "1") (pinfunction "1_1") (pintype "passive"))
      (node (ref "J2") (pin "13") (pinfunction "13_13") (pintype "passive"))
      (node (ref "J2") (pin "14") (pinfunction "14_14") (pintype "passive"))
      (node (ref "J3") (pin "1") (pinfunction "1_1") (pintype "passive"))
      (node (ref "J3") (pin "12") (pinfunction "12_12") (pintype "passive"))
      (node (ref "J3") (pin "15") (pinfunction "15_15") (pintype "passive"))
      (node (ref "J3") (pin "16") (pinfunction "16_16") (pintype "passive"))
      (node (ref "J3") (pin "2") (pinfunction "2_2") (pintype "passive"))
      (node (ref "J3") (pin "7") (pinfunction "7_7") (pintype "passive"))
      (node (ref "J3") (pin "8") (pinfunction "8_8") (pintype "passive"))
      (node (ref "J5") (pin "2") (pinfunction "2_2") (pintype "passive"))
      (node (ref "J5") (pin "4") (pinfunction "4_4") (pintype "passive"))
      (node (ref "P2") (pin "4") (pintype "passive"))
      (node (ref "P2") (pin "5") (pintype "passive"))
      (node (ref "R1") (pin "2") (pinfunction "2_2") (pintype "passive"))
      (node (ref "R2") (pin "1") (pinfunction "1_1") (pintype "passive"))
      (node (ref "R24") (pin "2") (pinfunction "2_2") (pintype "passive"))
      (node (ref "R25") (pin "1") (pinfunction "1_1") (pintype "passive"))
      (node (ref "R28") (pin "1") (pintype "passive"))
      (node (ref "R29") (pin "1") (pintype "passive"))
      (node (ref "R3") (pin "1") (pinfunction "1_1") (pintype "passive"))
      (node (ref "R4") (pin "2") (pinfunction "2_2") (pintype "passive"))
      (node (ref "U1") (pin "2") (pinfunction "VOUT_2") (pintype "passive"))
      (node (ref "U2") (pin "100") (pinfunction "VIO_3_100") (pintype "power_in"))
      (node (ref "U2") (pin "11") (pinfunction "VDD_5_11") (pintype "power_in"))
      (node (ref "U2") (pin "28") (pinfunction "VDD_4_28") (pintype "power_in"))
      (node (ref "U2") (pin "50") (pinfunction "VIO_1_50") (pintype "power_in"))
      (node (ref "U2") (pin "75") (pinfunction "VDD_2_75") (pintype "power_in"))
    )
    (net (code "113") (name "5V") (class "Default")
      (node (ref "C21") (pin "1") (pinfunction "1_1") (pintype "passive"))
      (node (ref "D1") (pin "1") (pinfunction "A_1") (pintype "passive"))
      (node (ref "D2") (pin "1") (pinfunction "A_1") (pintype "passive"))
      (node (ref "D3") (pin "1") (pinfunction "A_1") (pintype "passive"))
      (node (ref "F1") (pin "2") (pinfunction "2_2") (pintype "passive"))
      (node (ref "J2") (pin "1") (pinfunction "1_1") (pintype "passive"))
      (node (ref "J2") (pin "2") (pinfunction "2_2") (pintype "passive"))
      (node (ref "S3") (pin "1") (pinfunction "1_1") (pintype "passive"))
      (node (ref "U3") (pin "15") (pinfunction "VDD_15") (pintype "power_in"))
    )
    (net (code "114") (name "5V_USB") (class "Default")
      (node (ref "F1") (pin "1") (pinfunction "1_1") (pintype "passive"))
      (node (ref "P9") (pin "A4") (pinfunction "VBUS_A4") (pintype "bidirectional"))
      (node (ref "P9") (pin "B4") (pinfunction "VBUS_B4") (pintype "bidirectional"))
    )
    (net (code "115") (name "GND") (class "Default")
      (node (ref "C1") (pin "1") (pinfunction "1_1") (pintype "passive"))
      (node (ref "C10") (pin "1") (pinfunction "1_1") (pintype "passive"))
      (node (ref "C11") (pin "1") (pinfunction "1_1") (pintype "passive"))
      (node (ref "C12") (pin "2") (pinfunction "2_2") (pintype "passive"))
      (node (ref "C13") (pin "2") (pinfunction "2_2") (pintype "passive"))
      (node (ref "C14") (pin "1") (pinfunction "1_1") (pintype "passive"))
      (node (ref "C2") (pin "1") (pinfunction "1_1") (pintype "passive"))
      (node (ref "C21") (pin "2") (pinfunction "2_2") (pintype "passive"))
      (node (ref "C22") (pin "2") (pinfunction "2_2") (pintype "passive"))
      (node (ref "C3") (pin "2") (pinfunction "2_2") (pintype "passive"))
      (node (ref "C4") (pin "1") (pinfunction "1_1") (pintype "passive"))
      (node (ref "C46") (pin "2") (pinfunction "2_2") (pintype "passive"))
      (node (ref "C5") (pin "2") (pinfunction "2_2") (pintype "passive"))
      (node (ref "C6") (pin "2") (pinfunction "2_2") (pintype "passive"))
      (node (ref "C7") (pin "1") (pinfunction "1_1") (pintype "passive"))
      (node (ref "C8") (pin "1") (pinfunction "1_1") (pintype "passive"))
      (node (ref "C9") (pin "1") (pinfunction "1_1") (pintype "passive"))
      (node (ref "J2") (pin "7") (pinfunction "7_7") (pintype "passive"))
      (node (ref "J2") (pin "8") (pinfunction "8_8") (pintype "passive"))
      (node (ref "J3") (pin "20") (pinfunction "20_20") (pintype "passive"))
      (node (ref "J3") (pin "22") (pinfunction "22_22") (pintype "passive"))
      (node (ref "J3") (pin "25") (pinfunction "25_25") (pintype "passive"))
      (node (ref "J3") (pin "26") (pinfunction "26_26") (pintype "passive"))
      (node (ref "J3") (pin "5") (pinfunction "5_5") (pintype "passive"))
      (node (ref "J3") (pin "6") (pinfunction "6_6") (pintype "passive"))
      (node (ref "J3") (pin "9") (pinfunction "9_9") (pintype "passive"))
      (node (ref "J4") (pin "7") (pinfunction "7_7") (pintype "passive"))
      (node (ref "J5") (pin "6") (pinfunction "6_6") (pintype "passive"))
      (node (ref "J5") (pin "7") (pinfunction "7_7") (pintype "passive"))
      (node (ref "J7") (pin "4") (pinfunction "4_4") (pintype "passive"))
      (node (ref "P2") (pin "8") (pintype "passive"))
      (node (ref "P6") (pin "A1") (pinfunction "GND_A1") (pintype "bidirectional"))
      (node (ref "P6") (pin "B1") (pinfunction "GND_B1") (pintype "bidirectional"))
      (node (ref "P7") (pin "A1") (pinfunction "GND_A1") (pintype "bidirectional"))
      (node (ref "P7") (pin "B1") (pinfunction "GND_B1") (pintype "bidirectional"))
      (node (ref "P9") (pin "A1") (pinfunction "GND_A1") (pintype "bidirectional"))
      (node (ref "P9") (pin "B1") (pinfunction "GND_B1") (pintype "bidirectional"))
      (node (ref "PWR") (pin "2") (pinfunction "K_2") (pintype "passive"))
      (node (ref "R10") (pin "2") (pinfunction "2_2") (pintype "passive"))
      (node (ref "R11") (pin "2") (pinfunction "2_2") (pintype "passive"))
      (node (ref "R20") (pin "1") (pinfunction "1_1") (pintype "passive"))
      (node (ref "R21") (pin "1") (pinfunction "1_1") (pintype "passive"))
      (node (ref "R22") (pin "1") (pinfunction "1_1") (pintype "passive"))
      (node (ref "R23") (pin "1") (pinfunction "1_1") (pintype "passive"))
      (node (ref "R8") (pin "1") (pinfunction "1_1") (pintype "passive"))
      (node (ref "R9") (pin "1") (pinfunction "1_1") (pintype "passive"))
      (node (ref "S1") (pin "3") (pinfunction "B1_3") (pintype "passive"))
      (node (ref "S2") (pin "3") (pinfunction "B1_3") (pintype "passive"))
      (node (ref "U1") (pin "1") (pinfunction "GND_1") (pintype "passive"))
      (node (ref "U2") (pin "10") (pinfunction "VSS_5_10") (pintype "power_in"))
      (node (ref "U2") (pin "19") (pinfunction "VSSA_19") (pintype "power_in"))
      (node (ref "U2") (pin "27") (pinfunction "VSS_4_27") (pintype "power_in"))
      (node (ref "U2") (pin "49") (pinfunction "VSS_1_49") (pintype "power_in"))
      (node (ref "U2") (pin "74") (pinfunction "VSS_2_74") (pintype "power_in"))
      (node (ref "U2") (pin "99") (pinfunction "VSS_3_99") (pintype "power_in"))
      (node (ref "U3") (pin "14") (pinfunction "GND/VSS_14") (pintype "power_in"))
    )
    (net (code "116") (name "Net-(D1-K)") (class "Default")
      (node (ref "D1") (pin "2") (pinfunction "K_2") (pintype "passive"))
      (node (ref "R14") (pin "2") (pinfunction "2_2") (pintype "passive"))
    )
    (net (code "117") (name "Net-(D2-K)") (class "Default")
      (node (ref "D2") (pin "2") (pinfunction "K_2") (pintype "passive"))
      (node (ref "R13") (pin "2") (pinfunction "2_2") (pintype "passive"))
    )
    (net (code "118") (name "Net-(D3-K)") (class "Default")
      (node (ref "D3") (pin "2") (pinfunction "K_2") (pintype "passive"))
      (node (ref "R21") (pin "2") (pinfunction "2_2") (pintype "passive"))
    )
    (net (code "119") (name "Net-(J1-Pad2)") (class "Default")
      (node (ref "J1") (pin "2") (pinfunction "2_2") (pintype "passive"))
      (node (ref "R16") (pin "1") (pinfunction "1_1") (pintype "passive"))
    )
    (net (code "120") (name "Net-(J3-Pad3)") (class "Default")
      (node (ref "J3") (pin "3") (pinfunction "3_3") (pintype "passive"))
      (node (ref "R6") (pin "2") (pinfunction "2_2") (pintype "passive"))
    )
    (net (code "121") (name "Net-(J3-Pad4)") (class "Default")
      (node (ref "J3") (pin "4") (pinfunction "4_4") (pintype "passive"))
      (node (ref "R5") (pin "1") (pinfunction "1_1") (pintype "passive"))
    )
    (net (code "122") (name "Net-(J3-Pad10)") (class "Default")
      (node (ref "J3") (pin "10") (pinfunction "10_10") (pintype "passive"))
      (node (ref "J5") (pin "1") (pinfunction "1_1") (pintype "passive"))
    )
    (net (code "123") (name "Net-(LED1-A)") (class "Default")
      (node (ref "LED1") (pin "1") (pinfunction "A_1") (pintype "passive"))
      (node (ref "R2") (pin "2") (pinfunction "2_2") (pintype "passive"))
    )
    (net (code "124") (name "Net-(LED2-A)") (class "Default")
      (node (ref "LED2") (pin "1") (pinfunction "A_1") (pintype "passive"))
      (node (ref "R3") (pin "2") (pinfunction "2_2") (pintype "passive"))
    )
    (net (code "125") (name "Net-(P2-Pad9)") (class "Default")
      (node (ref "P2") (pin "9") (pintype "passive"))
      (node (ref "R28") (pin "2") (pintype "passive"))
    )
    (net (code "126") (name "Net-(P2-Pad12)") (class "Default")
      (node (ref "P2") (pin "12") (pintype "passive"))
      (node (ref "R29") (pin "2") (pintype "passive"))
    )
    (net (code "127") (name "Net-(P6-CC-PadA5)") (class "Default")
      (node (ref "P6") (pin "A5") (pinfunction "CC_A5") (pintype "bidirectional"))
      (node (ref "R20") (pin "2") (pinfunction "2_2") (pintype "passive"))
    )
    (net (code "128") (name "Net-(P6-CC-PadB5)") (class "Default")
      (node (ref "P6") (pin "B5") (pinfunction "CC_B5") (pintype "bidirectional"))
      (node (ref "R22") (pin "2") (pinfunction "2_2") (pintype "passive"))
    )
    (net (code "129") (name "Net-(P7-CC-PadA5)") (class "Default")
      (node (ref "P7") (pin "A5") (pinfunction "CC_A5") (pintype "bidirectional"))
      (node (ref "R8") (pin "2") (pinfunction "2_2") (pintype "passive"))
    )
    (net (code "130") (name "Net-(P7-CC-PadB5)") (class "Default")
      (node (ref "P7") (pin "B5") (pinfunction "CC_B5") (pintype "bidirectional"))
      (node (ref "R9") (pin "2") (pinfunction "2_2") (pintype "passive"))
    )
    (net (code "131") (name "Net-(P9-CC-PadA5)") (class "Default")
      (node (ref "P9") (pin "A5") (pinfunction "CC_A5") (pintype "bidirectional"))
      (node (ref "R10") (pin "1") (pinfunction "1_1") (pintype "passive"))
    )
    (net (code "132") (name "Net-(P9-CC-PadB5)") (class "Default")
      (node (ref "P9") (pin "B5") (pinfunction "CC_B5") (pintype "bidirectional"))
      (node (ref "R11") (pin "1") (pinfunction "1_1") (pintype "passive"))
    )
    (net (code "133") (name "Net-(PWR-A)") (class "Default")
      (node (ref "PWR") (pin "1") (pinfunction "A_1") (pintype "passive"))
      (node (ref "R1") (pin "1") (pinfunction "1_1") (pintype "passive"))
    )
    (net (code "134") (name "Net-(U1-VIN)") (class "Default")
      (node (ref "C12") (pin "1") (pinfunction "1_1") (pintype "passive"))
      (node (ref "F2") (pin "2") (pinfunction "2_2") (pintype "passive"))
      (node (ref "U1") (pin "3") (pinfunction "VIN_3") (pintype "passive"))
    )
    (net (code "135") (name "V33") (class "Default")
      (node (ref "C22") (pin "1") (pinfunction "1_1") (pintype "passive"))
      (node (ref "R16") (pin "2") (pinfunction "2_2") (pintype "passive"))
      (node (ref "U3") (pin "16") (pinfunction "V33_16") (pintype "power_in"))
    )
    (net (code "136") (name "unconnected-(P2-Pad7)") (class "Default")
      (node (ref "P2") (pin "7") (pintype "passive"))
    )
    (net (code "137") (name "unconnected-(P6-RFU1-PadA8)") (class "Default")
      (node (ref "P6") (pin "A8") (pinfunction "RFU1_A8") (pintype "bidirectional+no_connect"))
    )
    (net (code "138") (name "unconnected-(P6-RFU1-PadB8)") (class "Default")
      (node (ref "P6") (pin "B8") (pinfunction "RFU1_B8") (pintype "bidirectional+no_connect"))
    )
    (net (code "139") (name "unconnected-(P7-RFU1-PadA8)") (class "Default")
      (node (ref "P7") (pin "A8") (pinfunction "RFU1_A8") (pintype "bidirectional+no_connect"))
    )
    (net (code "140") (name "unconnected-(P7-RFU1-PadB8)") (class "Default")
      (node (ref "P7") (pin "B8") (pinfunction "RFU1_B8") (pintype "bidirectional+no_connect"))
    )
    (net (code "141") (name "unconnected-(P9-RFU1-PadA8)") (class "Default")
      (node (ref "P9") (pin "A8") (pinfunction "RFU1_A8") (pintype "bidirectional+no_connect"))
    )
    (net (code "142") (name "unconnected-(P9-RFU1-PadB8)") (class "Default")
      (node (ref "P9") (pin "B8") (pinfunction "RFU1_B8") (pintype "bidirectional+no_connect"))
    )
    (net (code "143") (name "unconnected-(S1-A1-Pad4)") (class "Default")
      (node (ref "S1") (pin "4") (pinfunction "A1_4") (pintype "passive"))
    )
    (net (code "144") (name "unconnected-(S1-B0-Pad2)") (class "Default")
      (node (ref "S1") (pin "2") (pinfunction "B0_2") (pintype "passive"))
    )
    (net (code "145") (name "unconnected-(S2-A1-Pad4)") (class "Default")
      (node (ref "S2") (pin "4") (pinfunction "A1_4") (pintype "passive"))
    )
    (net (code "146") (name "unconnected-(S2-B0-Pad2)") (class "Default")
      (node (ref "S2") (pin "2") (pinfunction "B0_2") (pintype "passive"))
    )
    (net (code "147") (name "unconnected-(S3-Pad2)") (class "Default")
      (node (ref "S3") (pin "2") (pinfunction "2_2") (pintype "passive"))
    )
    (net (code "148") (name "unconnected-(U3-P1.5{slash}MOSI{slash}PWM0_{slash}UCC2{slash}AIN5-Pad3)") (class "Default")
      (node (ref "U3") (pin "3") (pinfunction "P1.5/MOSI/PWM0_/UCC2/AIN5_3") (pintype "bidirectional+no_connect"))
    )
    (net (code "149") (name "unconnected-(U3-P2.2{slash}PWM3{slash}INT0_-Pad10)") (class "Default")
      (node (ref "U3") (pin "10") (pinfunction "P2.2/PWM3/INT0__10") (pintype "bidirectional+no_connect"))
    )
    (net (code "150") (name "unconnected-(U3-P2.4{slash}PWM1{slash}T2_{slash}CAP1_-Pad11)") (class "Default")
      (node (ref "U3") (pin "11") (pinfunction "P2.4/PWM1/T2_/CAP1__11") (pintype "bidirectional+no_connect"))
    )
    (net (code "151") (name "unconnected-(U3-P3.4{slash}T0-Pad9)") (class "Default")
      (node (ref "U3") (pin "9") (pinfunction "P3.4/T0_9") (pintype "bidirectional+no_connect"))
    )
    (net (code "152") (name "unconnected-(U3-P5.7{slash}RST-Pad6)") (class "Default")
      (node (ref "U3") (pin "6") (pinfunction "P5.7/RST_6") (pintype "input+no_connect"))
    )
  )
)
